# mirsot_sch-final.net
KiCad netlist of a schematic drawn in EAGLE
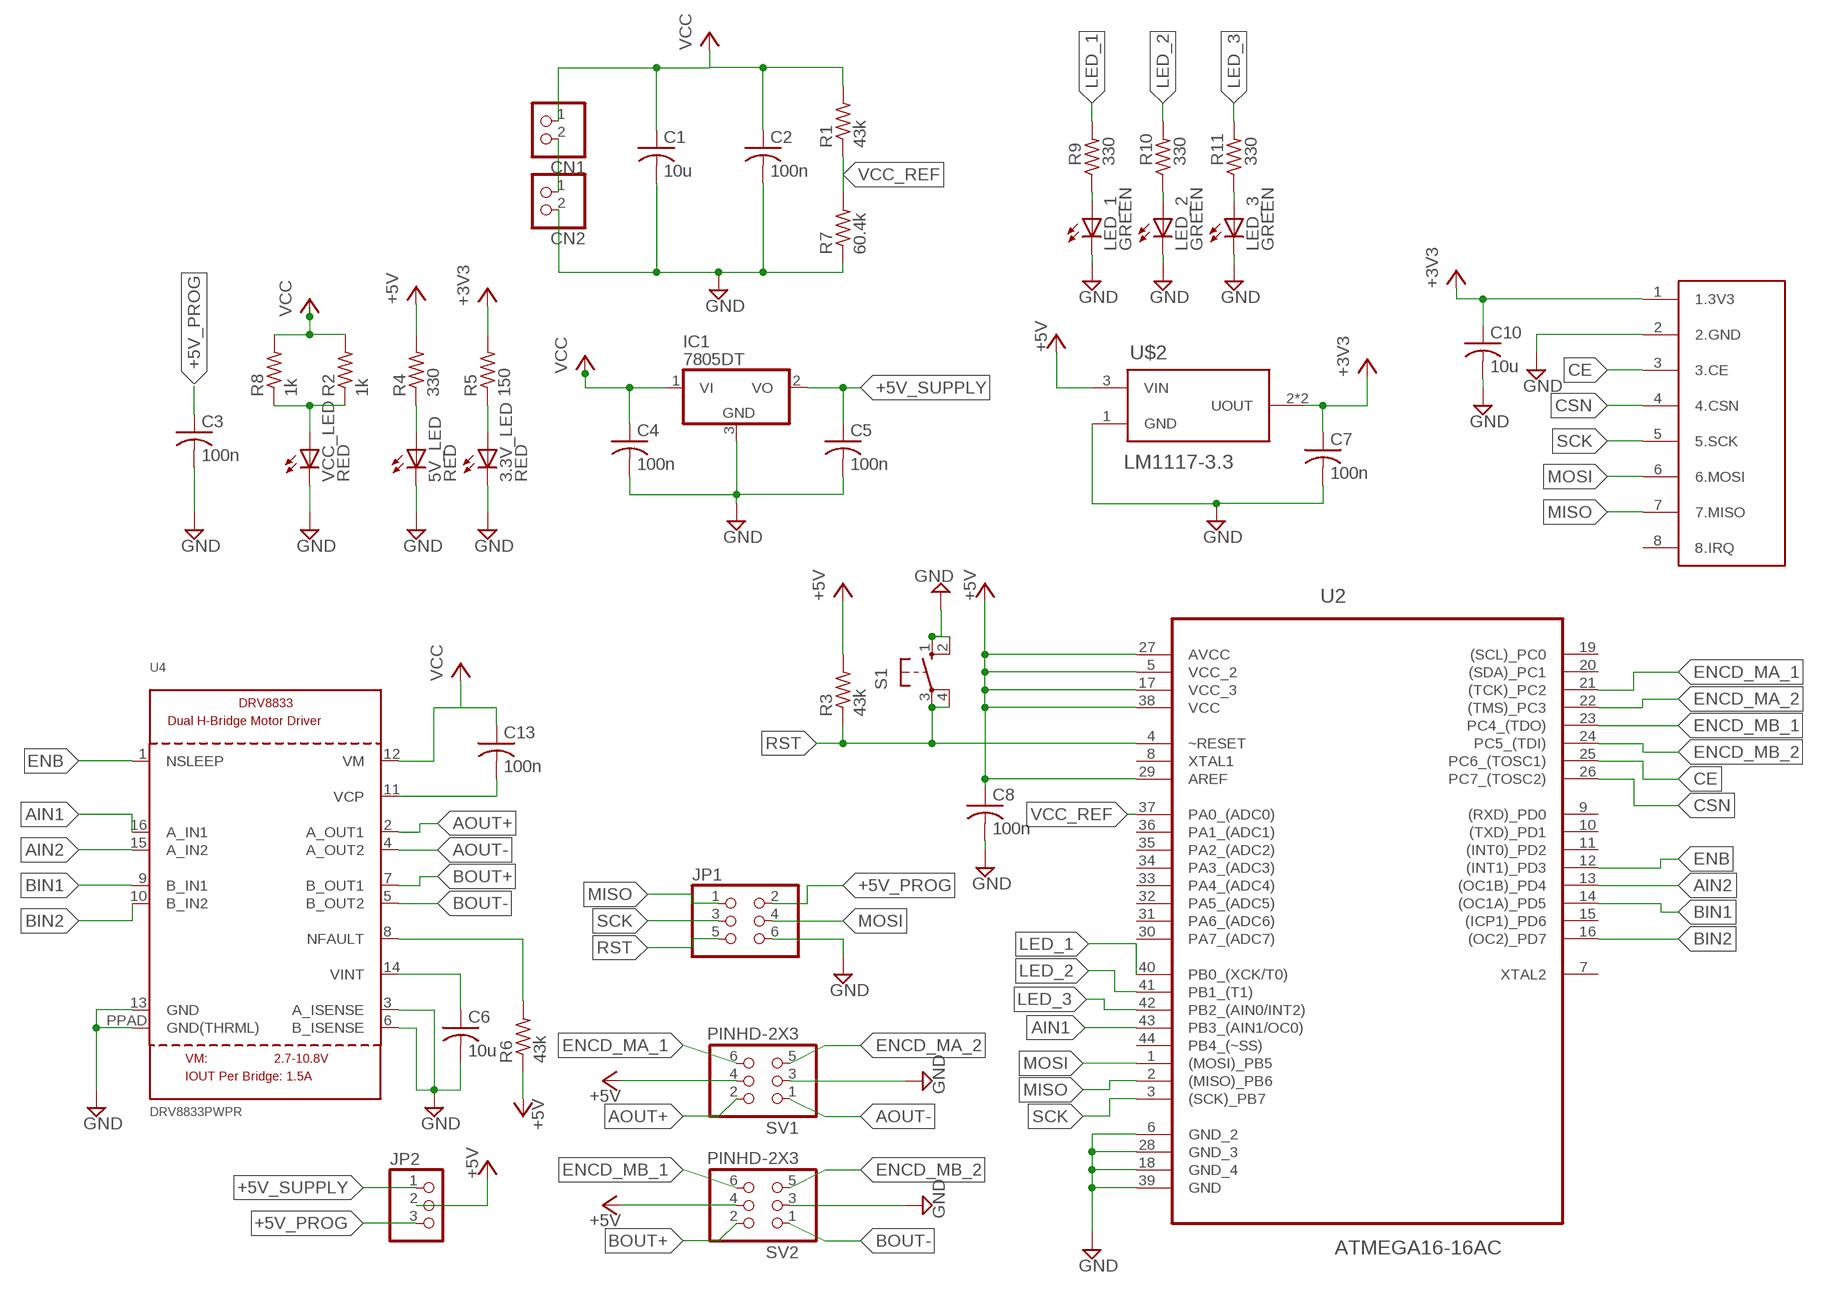
[diagram p0: schematic, sheet 1]

(export (version "E")
  (design (tool "Eeschema 10.0.6"))
  (components
    (comp (ref "3.3V_LED")
      (value "RED")
      (footprint "eagle-import:CHIPLED_0603")
      (libsource (lib "eagle-import") (part "LEDCHIPLED_0603"))
    )
    (comp (ref "5V_LED")
      (value "RED")
      (footprint "eagle-import:CHIPLED_0603")
      (libsource (lib "eagle-import") (part "LEDCHIPLED_0603"))
    )
    (comp (ref "C1")
      (value "10u")
      (footprint "eagle-import:C0603")
      (libsource (lib "eagle-import") (part "C-USC0603"))
    )
    (comp (ref "C2")
      (value "100n")
      (footprint "eagle-import:C0603")
      (libsource (lib "eagle-import") (part "C-USC0603"))
    )
    (comp (ref "C3")
      (value "100n")
      (footprint "eagle-import:C0603")
      (libsource (lib "eagle-import") (part "C-USC0603"))
    )
    (comp (ref "C4")
      (value "100n")
      (footprint "eagle-import:C0603")
      (libsource (lib "eagle-import") (part "C-USC0603"))
    )
    (comp (ref "C5")
      (value "100n")
      (footprint "eagle-import:C0603")
      (libsource (lib "eagle-import") (part "C-USC0603"))
    )
    (comp (ref "C6")
      (value "10u")
      (footprint "eagle-import:C0603")
      (libsource (lib "eagle-import") (part "C-USC0603"))
    )
    (comp (ref "C7")
      (value "100n")
      (footprint "eagle-import:C0603")
      (libsource (lib "eagle-import") (part "C-USC0603"))
    )
    (comp (ref "C8")
      (value "100n")
      (footprint "eagle-import:C0603")
      (libsource (lib "eagle-import") (part "C-USC0603"))
    )
    (comp (ref "C10")
      (value "10u")
      (footprint "eagle-import:C0603")
      (libsource (lib "eagle-import") (part "C-USC0603"))
    )
    (comp (ref "C13")
      (value "100n")
      (footprint "eagle-import:C0603")
      (libsource (lib "eagle-import") (part "C-USC0603"))
    )
    (comp (ref "CN1")
      (value "JST_2PIN-THM")
      (footprint "eagle-import:JST-PH-2-THM")
      (libsource (lib "eagle-import") (part "JST_2PIN-THM"))
    )
    (comp (ref "CN2")
      (value "JST_2PIN-THM")
      (footprint "eagle-import:JST-PH-2-THM")
      (libsource (lib "eagle-import") (part "JST_2PIN-THM"))
    )
    (comp (ref "IC1")
      (value "7805DT")
      (footprint "eagle-import:TO252")
      (libsource (lib "eagle-import") (part "78DT05"))
    )
    (comp (ref "JP1")
      (value "PINHD-2X3")
      (footprint "eagle-import:2X03")
      (libsource (lib "eagle-import") (part "pinhead_325_PINHD-2X3"))
    )
    (comp (ref "JP2")
      (value "PINHD-1X3")
      (footprint "eagle-import:1X03")
      (libsource (lib "eagle-import") (part "PINHD-1X3"))
    )
    (comp (ref "LED_1")
      (value "GREEN")
      (footprint "eagle-import:CHIPLED_0603")
      (libsource (lib "eagle-import") (part "LEDCHIPLED_0603"))
    )
    (comp (ref "LED_2")
      (value "GREEN")
      (footprint "eagle-import:CHIPLED_0603")
      (libsource (lib "eagle-import") (part "LEDCHIPLED_0603"))
    )
    (comp (ref "LED_3")
      (value "GREEN")
      (footprint "eagle-import:CHIPLED_0603")
      (libsource (lib "eagle-import") (part "LEDCHIPLED_0603"))
    )
    (comp (ref "R1")
      (value "43k")
      (footprint "eagle-import:R1206")
      (libsource (lib "eagle-import") (part "R-US_R1206"))
    )
    (comp (ref "R2")
      (value "1k")
      (footprint "eagle-import:R1206")
      (libsource (lib "eagle-import") (part "R-US_R1206"))
    )
    (comp (ref "R3")
      (value "43k")
      (footprint "eagle-import:R1206")
      (libsource (lib "eagle-import") (part "R-US_R1206"))
    )
    (comp (ref "R4")
      (value "330")
      (footprint "eagle-import:R1206")
      (libsource (lib "eagle-import") (part "R-US_R1206"))
    )
    (comp (ref "R5")
      (value "150")
      (footprint "eagle-import:R2512")
      (libsource (lib "eagle-import") (part "R-US_R2512"))
    )
    (comp (ref "R6")
      (value "43k")
      (footprint "eagle-import:R1206")
      (libsource (lib "eagle-import") (part "R-US_R1206"))
    )
    (comp (ref "R7")
      (value "60.4k")
      (footprint "eagle-import:R1206")
      (libsource (lib "eagle-import") (part "R-US_R1206"))
    )
    (comp (ref "R8")
      (value "1k")
      (footprint "eagle-import:R1206")
      (libsource (lib "eagle-import") (part "R-US_R1206"))
    )
    (comp (ref "R9")
      (value "330")
      (footprint "eagle-import:R1206")
      (libsource (lib "eagle-import") (part "R-US_R1206"))
    )
    (comp (ref "R10")
      (value "330")
      (footprint "eagle-import:R1206")
      (libsource (lib "eagle-import") (part "R-US_R1206"))
    )
    (comp (ref "R11")
      (value "330")
      (footprint "eagle-import:R1206")
      (libsource (lib "eagle-import") (part "R-US_R1206"))
    )
    (comp (ref "S1")
      (value "10-XX")
      (footprint "eagle-import:B3F-10XX")
      (fields (field (name "MPN") "B3F-1000"))
      (libsource (lib "eagle-import") (part "10-XX"))
    )
    (comp (ref "SV1")
      (value "PINHD-2X3")
      (footprint "eagle-import:2X03")
      (libsource (lib "eagle-import") (part "PINHD-2X3"))
    )
    (comp (ref "SV2")
      (value "PINHD-2X3")
      (footprint "eagle-import:2X03")
      (libsource (lib "eagle-import") (part "PINHD-2X3"))
    )
    (comp (ref "U$1")
      (value "NRF24L01+")
      (footprint "eagle-import:NRF24L01+")
      (libsource (lib "eagle-import") (part "NRF24L01+"))
    )
    (comp (ref "U$2")
      (value "LM1117-3.3")
      (footprint "eagle-import:SOT-223")
      (fields (field (name "MF") "Texas Instruments"))
      (libsource (lib "eagle-import") (part "LM1117-3.3"))
    )
    (comp (ref "U2")
      (value "ATMEGA16-16AC")
      (footprint "eagle-import:QFP80P1200X1200X120-44N")
      (fields (field (name "MF") "Microchip"))
      (libsource (lib "eagle-import") (part "ATMEGA16-16AC"))
    )
    (comp (ref "U4")
      (value "DRV8833PWPR")
      (footprint "eagle-import:HTSSOP16")
      (libsource (lib "eagle-import") (part "DRV8833"))
    )
    (comp (ref "VCC_LED")
      (value "RED")
      (footprint "eagle-import:CHIPLED_0603")
      (libsource (lib "eagle-import") (part "LEDCHIPLED_0603"))
    )
  )
  (nets
    (net (code "1") (name "+3V3") (class "Default")
      (node (ref "C10") (pin "1") (pinfunction "1_1") (pintype "passive"))
      (node (ref "C7") (pin "1") (pinfunction "1_1") (pintype "passive"))
      (node (ref "R5") (pin "2") (pinfunction "2_2") (pintype "passive"))
      (node (ref "U$1") (pin "1") (pinfunction "1.3V3_1") (pintype "bidirectional"))
      (node (ref "U$2") (pin "2") (pinfunction "UOUT_2") (pintype "output"))
      (node (ref "U$2") (pin "4") (pinfunction "UOUT_4") (pintype "output"))
    )
    (net (code "2") (name "+5V") (class "Default")
      (node (ref "C8") (pin "1") (pinfunction "1_1") (pintype "passive"))
      (node (ref "JP2") (pin "2") (pinfunction "2_2") (pintype "passive"))
      (node (ref "R3") (pin "2") (pinfunction "2_2") (pintype "passive"))
      (node (ref "R4") (pin "2") (pinfunction "2_2") (pintype "passive"))
      (node (ref "R6") (pin "1") (pinfunction "1_1") (pintype "passive"))
      (node (ref "SV1") (pin "4") (pinfunction "4_4") (pintype "passive"))
      (node (ref "SV2") (pin "4") (pinfunction "4_4") (pintype "passive"))
      (node (ref "U$2") (pin "3") (pinfunction "VIN_3") (pintype "bidirectional"))
      (node (ref "U2") (pin "17") (pinfunction "VCC_3_17") (pintype "power_in"))
      (node (ref "U2") (pin "27") (pinfunction "AVCC_27") (pintype "power_in"))
      (node (ref "U2") (pin "29") (pinfunction "AREF_29") (pintype "input"))
      (node (ref "U2") (pin "38") (pinfunction "VCC_38") (pintype "power_in"))
      (node (ref "U2") (pin "5") (pinfunction "VCC_2_5") (pintype "power_in"))
    )
    (net (code "3") (name "+5V_PROG") (class "Default")
      (node (ref "C3") (pin "1") (pinfunction "1_1") (pintype "passive"))
      (node (ref "JP1") (pin "2") (pinfunction "2_2") (pintype "passive"))
      (node (ref "JP2") (pin "3") (pinfunction "3_3") (pintype "passive"))
    )
    (net (code "4") (name "+5V_SUPPLY") (class "Default")
      (node (ref "C5") (pin "1") (pinfunction "1_1") (pintype "passive"))
      (node (ref "IC1") (pin "2") (pinfunction "VO_2") (pintype "passive"))
      (node (ref "JP2") (pin "1") (pinfunction "1_1") (pintype "passive"))
    )
    (net (code "5") (name "AIN1") (class "Default")
      (node (ref "U2") (pin "43") (pinfunction "PB3_(AIN1/OC0)_43") (pintype "bidirectional"))
      (node (ref "U4") (pin "16") (pinfunction "A_IN1_16") (pintype "input"))
    )
    (net (code "6") (name "AIN2") (class "Default")
      (node (ref "U2") (pin "13") (pinfunction "(OC1B)_PD4_13") (pintype "bidirectional"))
      (node (ref "U4") (pin "15") (pinfunction "A_IN2_15") (pintype "input"))
    )
    (net (code "7") (name "AOUT+") (class "Default")
      (node (ref "SV1") (pin "2") (pinfunction "2_2") (pintype "passive"))
      (node (ref "U4") (pin "2") (pinfunction "A_OUT1_2") (pintype "output"))
    )
    (net (code "8") (name "AOUT-") (class "Default")
      (node (ref "SV1") (pin "1") (pinfunction "1_1") (pintype "passive"))
      (node (ref "U4") (pin "4") (pinfunction "A_OUT2_4") (pintype "output"))
    )
    (net (code "9") (name "BIN1") (class "Default")
      (node (ref "U2") (pin "14") (pinfunction "(OC1A)_PD5_14") (pintype "bidirectional"))
      (node (ref "U4") (pin "9") (pinfunction "B_IN1_9") (pintype "input"))
    )
    (net (code "10") (name "BIN2") (class "Default")
      (node (ref "U2") (pin "16") (pinfunction "(OC2)_PD7_16") (pintype "bidirectional"))
      (node (ref "U4") (pin "10") (pinfunction "B_IN2_10") (pintype "input"))
    )
    (net (code "11") (name "BOUT+") (class "Default")
      (node (ref "SV2") (pin "2") (pinfunction "2_2") (pintype "passive"))
      (node (ref "U4") (pin "7") (pinfunction "B_OUT1_7") (pintype "output"))
    )
    (net (code "12") (name "BOUT-") (class "Default")
      (node (ref "SV2") (pin "1") (pinfunction "1_1") (pintype "passive"))
      (node (ref "U4") (pin "5") (pinfunction "B_OUT2_5") (pintype "output"))
    )
    (net (code "13") (name "CE") (class "Default")
      (node (ref "U$1") (pin "3") (pinfunction "3.CE_3") (pintype "bidirectional"))
      (node (ref "U2") (pin "25") (pinfunction "PC6_(TOSC1)_25") (pintype "bidirectional"))
    )
    (net (code "14") (name "CSN") (class "Default")
      (node (ref "U$1") (pin "4") (pinfunction "4.CSN_4") (pintype "bidirectional"))
      (node (ref "U2") (pin "26") (pinfunction "PC7_(TOSC2)_26") (pintype "bidirectional"))
    )
    (net (code "15") (name "ENB") (class "Default")
      (node (ref "U2") (pin "12") (pinfunction "(INT1)_PD3_12") (pintype "bidirectional"))
      (node (ref "U4") (pin "1") (pinfunction "NSLEEP_1") (pintype "input"))
    )
    (net (code "16") (name "ENCD_MA_1") (class "Default")
      (node (ref "SV1") (pin "6") (pinfunction "6_6") (pintype "passive"))
      (node (ref "U2") (pin "21") (pinfunction "(TCK)_PC2_21") (pintype "bidirectional"))
    )
    (net (code "17") (name "ENCD_MA_2") (class "Default")
      (node (ref "SV1") (pin "5") (pinfunction "5_5") (pintype "passive"))
      (node (ref "U2") (pin "22") (pinfunction "(TMS)_PC3_22") (pintype "bidirectional"))
    )
    (net (code "18") (name "ENCD_MB_1") (class "Default")
      (node (ref "SV2") (pin "6") (pinfunction "6_6") (pintype "passive"))
      (node (ref "U2") (pin "23") (pinfunction "PC4_(TDO)_23") (pintype "bidirectional"))
    )
    (net (code "19") (name "ENCD_MB_2") (class "Default")
      (node (ref "SV2") (pin "5") (pinfunction "5_5") (pintype "passive"))
      (node (ref "U2") (pin "24") (pinfunction "PC5_(TDI)_24") (pintype "bidirectional"))
    )
    (net (code "20") (name "GND") (class "Default")
      (node (ref "3.3V_LED") (pin "C") (pinfunction "C_C") (pintype "passive"))
      (node (ref "5V_LED") (pin "C") (pinfunction "C_C") (pintype "passive"))
      (node (ref "C1") (pin "2") (pinfunction "2_2") (pintype "passive"))
      (node (ref "C10") (pin "2") (pinfunction "2_2") (pintype "passive"))
      (node (ref "C2") (pin "2") (pinfunction "2_2") (pintype "passive"))
      (node (ref "C3") (pin "2") (pinfunction "2_2") (pintype "passive"))
      (node (ref "C4") (pin "2") (pinfunction "2_2") (pintype "passive"))
      (node (ref "C5") (pin "2") (pinfunction "2_2") (pintype "passive"))
      (node (ref "C6") (pin "2") (pinfunction "2_2") (pintype "passive"))
      (node (ref "C7") (pin "2") (pinfunction "2_2") (pintype "passive"))
      (node (ref "C8") (pin "2") (pinfunction "2_2") (pintype "passive"))
      (node (ref "CN2") (pin "2") (pinfunction "1_2") (pintype "passive"))
      (node (ref "IC1") (pin "3") (pinfunction "GND_3") (pintype "passive"))
      (node (ref "JP1") (pin "6") (pinfunction "6_6") (pintype "passive"))
      (node (ref "LED_1") (pin "C") (pinfunction "C_C") (pintype "passive"))
      (node (ref "LED_2") (pin "C") (pinfunction "C_C") (pintype "passive"))
      (node (ref "LED_3") (pin "C") (pinfunction "C_C") (pintype "passive"))
      (node (ref "R7") (pin "1") (pinfunction "1_1") (pintype "passive"))
      (node (ref "S1") (pin "1") (pinfunction "S_1") (pintype "passive"))
      (node (ref "S1") (pin "2") (pinfunction "S1_2") (pintype "passive"))
      (node (ref "SV1") (pin "3") (pinfunction "3_3") (pintype "passive"))
      (node (ref "SV2") (pin "3") (pinfunction "3_3") (pintype "passive"))
      (node (ref "U$1") (pin "2") (pinfunction "2.GND_2") (pintype "bidirectional"))
      (node (ref "U$2") (pin "1") (pinfunction "GND_1") (pintype "passive"))
      (node (ref "U2") (pin "18") (pinfunction "GND_4_18") (pintype "passive"))
      (node (ref "U2") (pin "28") (pinfunction "GND_3_28") (pintype "passive"))
      (node (ref "U2") (pin "39") (pinfunction "GND_39") (pintype "passive"))
      (node (ref "U2") (pin "6") (pinfunction "GND_2_6") (pintype "passive"))
      (node (ref "U4") (pin "13") (pinfunction "GND_13") (pintype "power_in"))
      (node (ref "U4") (pin "3") (pinfunction "A_ISENSE_3") (pintype "bidirectional"))
      (node (ref "U4") (pin "6") (pinfunction "B_ISENSE_6") (pintype "bidirectional"))
      (node (ref "U4") (pin "PPAD") (pinfunction "GND(THRML)_PPAD") (pintype "power_in"))
      (node (ref "VCC_LED") (pin "C") (pinfunction "C_C") (pintype "passive"))
    )
    (net (code "21") (name "LED_1") (class "Default")
      (node (ref "R9") (pin "2") (pinfunction "2_2") (pintype "passive"))
      (node (ref "U2") (pin "40") (pinfunction "PB0_(XCK/T0)_40") (pintype "bidirectional"))
    )
    (net (code "22") (name "LED_2") (class "Default")
      (node (ref "R10") (pin "2") (pinfunction "2_2") (pintype "passive"))
      (node (ref "U2") (pin "41") (pinfunction "PB1_(T1)_41") (pintype "bidirectional"))
    )
    (net (code "23") (name "LED_3") (class "Default")
      (node (ref "R11") (pin "2") (pinfunction "2_2") (pintype "passive"))
      (node (ref "U2") (pin "42") (pinfunction "PB2_(AIN0/INT2)_42") (pintype "bidirectional"))
    )
    (net (code "24") (name "MISO") (class "Default")
      (node (ref "JP1") (pin "1") (pinfunction "1_1") (pintype "passive"))
      (node (ref "U$1") (pin "7") (pinfunction "7.MISO_7") (pintype "bidirectional"))
      (node (ref "U2") (pin "2") (pinfunction "(MISO)_PB6_2") (pintype "bidirectional"))
    )
    (net (code "25") (name "MOSI") (class "Default")
      (node (ref "JP1") (pin "4") (pinfunction "4_4") (pintype "passive"))
      (node (ref "U$1") (pin "6") (pinfunction "6.MOSI_6") (pintype "bidirectional"))
      (node (ref "U2") (pin "1") (pinfunction "(MOSI)_PB5_1") (pintype "bidirectional"))
    )
    (net (code "26") (name "Net-(3.3V_LED-PadA)") (class "Default")
      (node (ref "3.3V_LED") (pin "A") (pinfunction "A_A") (pintype "passive"))
      (node (ref "R5") (pin "1") (pinfunction "1_1") (pintype "passive"))
    )
    (net (code "27") (name "Net-(5V_LED-PadA)") (class "Default")
      (node (ref "5V_LED") (pin "A") (pinfunction "A_A") (pintype "passive"))
      (node (ref "R4") (pin "1") (pinfunction "1_1") (pintype "passive"))
    )
    (net (code "28") (name "Net-(CN1-1)") (class "Default")
      (node (ref "CN1") (pin "2") (pinfunction "1_2") (pintype "passive"))
      (node (ref "CN2") (pin "1") (pinfunction "2_1") (pintype "passive"))
    )
    (net (code "29") (name "Net-(LED_1-PadA)") (class "Default")
      (node (ref "LED_1") (pin "A") (pinfunction "A_A") (pintype "passive"))
      (node (ref "R9") (pin "1") (pinfunction "1_1") (pintype "passive"))
    )
    (net (code "30") (name "Net-(LED_2-PadA)") (class "Default")
      (node (ref "LED_2") (pin "A") (pinfunction "A_A") (pintype "passive"))
      (node (ref "R10") (pin "1") (pinfunction "1_1") (pintype "passive"))
    )
    (net (code "31") (name "Net-(LED_3-PadA)") (class "Default")
      (node (ref "LED_3") (pin "A") (pinfunction "A_A") (pintype "passive"))
      (node (ref "R11") (pin "1") (pinfunction "1_1") (pintype "passive"))
    )
    (net (code "32") (name "Net-(R2-Pad1)") (class "Default")
      (node (ref "R2") (pin "1") (pinfunction "1_1") (pintype "passive"))
      (node (ref "R8") (pin "1") (pinfunction "1_1") (pintype "passive"))
      (node (ref "VCC_LED") (pin "A") (pinfunction "A_A") (pintype "passive"))
    )
    (net (code "33") (name "Net-(U4-NFAULT)") (class "Default")
      (node (ref "R6") (pin "2") (pinfunction "2_2") (pintype "passive"))
      (node (ref "U4") (pin "8") (pinfunction "NFAULT_8") (pintype "bidirectional"))
    )
    (net (code "34") (name "Net-(U4-VCP)") (class "Default")
      (node (ref "C13") (pin "2") (pinfunction "2_2") (pintype "passive"))
      (node (ref "U4") (pin "11") (pinfunction "VCP_11") (pintype "bidirectional"))
    )
    (net (code "35") (name "Net-(U4-VINT)") (class "Default")
      (node (ref "C6") (pin "1") (pinfunction "1_1") (pintype "passive"))
      (node (ref "U4") (pin "14") (pinfunction "VINT_14") (pintype "power_in"))
    )
    (net (code "36") (name "RST") (class "Default")
      (node (ref "JP1") (pin "5") (pinfunction "5_5") (pintype "passive"))
      (node (ref "R3") (pin "1") (pinfunction "1_1") (pintype "passive"))
      (node (ref "S1") (pin "3") (pinfunction "P_3") (pintype "passive"))
      (node (ref "S1") (pin "4") (pinfunction "P1_4") (pintype "passive"))
      (node (ref "U2") (pin "4") (pinfunction "~{RESET}_4") (pintype "input"))
    )
    (net (code "37") (name "SCK") (class "Default")
      (node (ref "JP1") (pin "3") (pinfunction "3_3") (pintype "passive"))
      (node (ref "U$1") (pin "5") (pinfunction "5.SCK_5") (pintype "bidirectional"))
      (node (ref "U2") (pin "3") (pinfunction "(SCK)_PB7_3") (pintype "bidirectional"))
    )
    (net (code "38") (name "VCC") (class "Default")
      (node (ref "C1") (pin "1") (pinfunction "1_1") (pintype "passive"))
      (node (ref "C13") (pin "1") (pinfunction "1_1") (pintype "passive"))
      (node (ref "C2") (pin "1") (pinfunction "1_1") (pintype "passive"))
      (node (ref "C4") (pin "1") (pinfunction "1_1") (pintype "passive"))
      (node (ref "CN1") (pin "1") (pinfunction "2_1") (pintype "passive"))
      (node (ref "IC1") (pin "1") (pinfunction "VI_1") (pintype "input"))
      (node (ref "R1") (pin "2") (pinfunction "2_2") (pintype "passive"))
      (node (ref "R2") (pin "2") (pinfunction "2_2") (pintype "passive"))
      (node (ref "R8") (pin "2") (pinfunction "2_2") (pintype "passive"))
      (node (ref "U4") (pin "12") (pinfunction "VM_12") (pintype "power_in"))
    )
    (net (code "39") (name "VCC_REF") (class "Default")
      (node (ref "R1") (pin "1") (pinfunction "1_1") (pintype "passive"))
      (node (ref "R7") (pin "2") (pinfunction "2_2") (pintype "passive"))
      (node (ref "U2") (pin "37") (pinfunction "PA0_(ADC0)_37") (pintype "bidirectional"))
    )
    (net (code "40") (name "unconnected-(U$1-8.IRQ-Pad8)") (class "Default")
      (node (ref "U$1") (pin "8") (pinfunction "8.IRQ_8") (pintype "bidirectional"))
    )
    (net (code "41") (name "unconnected-(U2-(ICP1)_PD6-Pad15)") (class "Default")
      (node (ref "U2") (pin "15") (pinfunction "(ICP1)_PD6_15") (pintype "bidirectional"))
    )
    (net (code "42") (name "unconnected-(U2-(INT0)_PD2-Pad11)") (class "Default")
      (node (ref "U2") (pin "11") (pinfunction "(INT0)_PD2_11") (pintype "bidirectional"))
    )
    (net (code "43") (name "unconnected-(U2-(RXD)_PD0-Pad9)") (class "Default")
      (node (ref "U2") (pin "9") (pinfunction "(RXD)_PD0_9") (pintype "bidirectional"))
    )
    (net (code "44") (name "unconnected-(U2-(SCL)_PC0-Pad19)") (class "Default")
      (node (ref "U2") (pin "19") (pinfunction "(SCL)_PC0_19") (pintype "bidirectional"))
    )
    (net (code "45") (name "unconnected-(U2-(SDA)_PC1-Pad20)") (class "Default")
      (node (ref "U2") (pin "20") (pinfunction "(SDA)_PC1_20") (pintype "bidirectional"))
    )
    (net (code "46") (name "unconnected-(U2-(TXD)_PD1-Pad10)") (class "Default")
      (node (ref "U2") (pin "10") (pinfunction "(TXD)_PD1_10") (pintype "bidirectional"))
    )
    (net (code "47") (name "unconnected-(U2-PA1_(ADC1)-Pad36)") (class "Default")
      (node (ref "U2") (pin "36") (pinfunction "PA1_(ADC1)_36") (pintype "bidirectional"))
    )
    (net (code "48") (name "unconnected-(U2-PA2_(ADC2)-Pad35)") (class "Default")
      (node (ref "U2") (pin "35") (pinfunction "PA2_(ADC2)_35") (pintype "bidirectional"))
    )
    (net (code "49") (name "unconnected-(U2-PA3_(ADC3)-Pad34)") (class "Default")
      (node (ref "U2") (pin "34") (pinfunction "PA3_(ADC3)_34") (pintype "bidirectional"))
    )
    (net (code "50") (name "unconnected-(U2-PA4_(ADC4)-Pad33)") (class "Default")
      (node (ref "U2") (pin "33") (pinfunction "PA4_(ADC4)_33") (pintype "bidirectional"))
    )
    (net (code "51") (name "unconnected-(U2-PA5_(ADC5)-Pad32)") (class "Default")
      (node (ref "U2") (pin "32") (pinfunction "PA5_(ADC5)_32") (pintype "bidirectional"))
    )
    (net (code "52") (name "unconnected-(U2-PA6_(ADC6)-Pad31)") (class "Default")
      (node (ref "U2") (pin "31") (pinfunction "PA6_(ADC6)_31") (pintype "bidirectional"))
    )
    (net (code "53") (name "unconnected-(U2-PA7_(ADC7)-Pad30)") (class "Default")
      (node (ref "U2") (pin "30") (pinfunction "PA7_(ADC7)_30") (pintype "bidirectional"))
    )
    (net (code "54") (name "unconnected-(U2-PB4_(~{SS})-Pad44)") (class "Default")
      (node (ref "U2") (pin "44") (pinfunction "PB4_(~{SS})_44") (pintype "bidirectional"))
    )
    (net (code "55") (name "unconnected-(U2-XTAL1-Pad8)") (class "Default")
      (node (ref "U2") (pin "8") (pinfunction "XTAL1_8") (pintype "input"))
    )
    (net (code "56") (name "unconnected-(U2-XTAL2-Pad7)") (class "Default")
      (node (ref "U2") (pin "7") (pinfunction "XTAL2_7") (pintype "output"))
    )
  )
)
